# 1_-_Power.net
KiCad netlist of a schematic drawn in Altium Designer
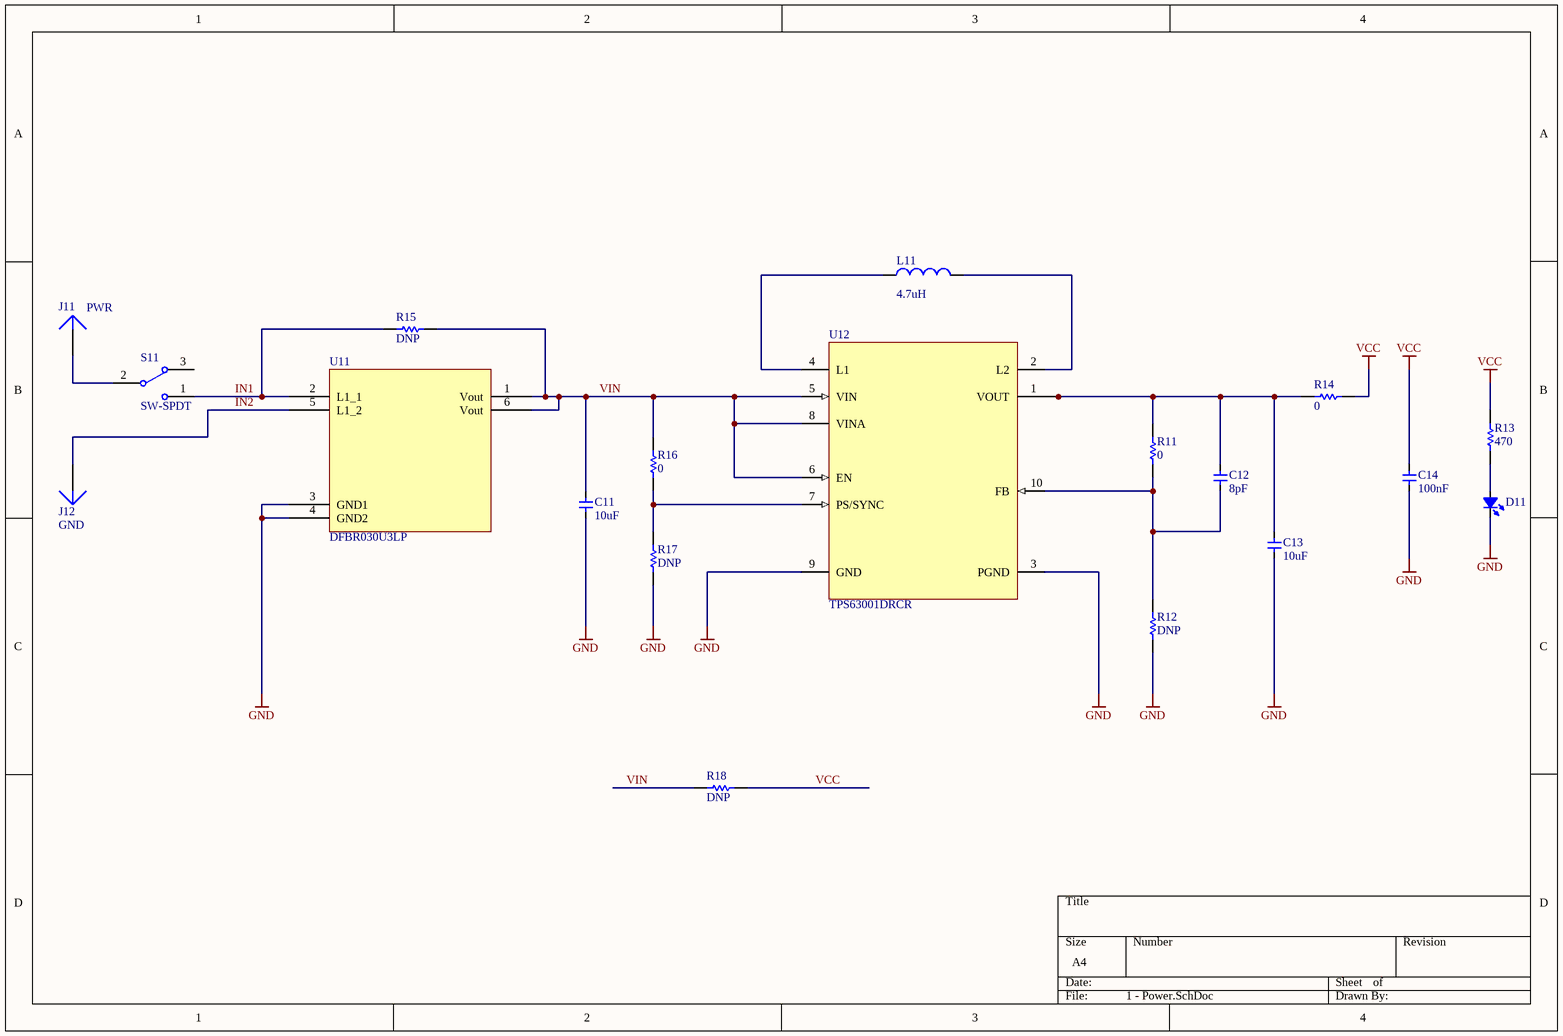
[diagram p0: 1 - Power.SchDoc]

(export (version "E")
  (design (tool "Eeschema 10.0.6"))
  (components
    (comp (ref "C11")
      (value "10uF")
      (footprint "CAPC2012X135N")
      (description "Capacitor")
      (fields (field (name "Comment") "Cap_0603"))
      (libsource (lib "SCH_Passive") (part "Cap_0603"))
    )
    (comp (ref "C12")
      (value "8pF")
      (footprint "PCB_PassiveCap:CAP_0603")
      (description "Capacitor")
      (fields (field (name "Comment") "Cap_0603"))
      (libsource (lib "SCH_Passive") (part "Cap_0603"))
    )
    (comp (ref "C13")
      (value "10uF")
      (footprint "CAPC2012X135N")
      (description "Capacitor")
      (fields (field (name "Comment") "Cap_0603"))
      (libsource (lib "SCH_Passive") (part "Cap_0603"))
    )
    (comp (ref "C14")
      (value "100nF")
      (footprint "PCB_PassiveCap:CAP_0603")
      (description "Capacitor")
      (fields (field (name "Comment") "Cap_0603"))
      (libsource (lib "SCH_Passive") (part "Cap_0603"))
    )
    (comp (ref "D11")
      (value "LED_0603")
      (footprint "PCB_ActiveLED:LED_0603_RED")
      (description "LED")
      (libsource (lib "SCH_Active") (part "LED_0603"))
    )
    (comp (ref "J11")
      (value "PWR")
      (footprint "PIN1")
      (description "Plug")
      (fields (field (name "PUBLISHER") "Altium Limited"))
      (libsource (lib "Miscellaneous Connectors") (part "Plug"))
    )
    (comp (ref "J12")
      (value "GND")
      (footprint "PIN1")
      (description "Plug")
      (fields (field (name "PUBLISHER") "Altium Limited"))
      (libsource (lib "Miscellaneous Connectors") (part "Plug"))
    )
    (comp (ref "L11")
      (value "4.7uH")
      (footprint "RES_0805")
      (description "Inductor")
      (fields (field (name "PUBLISHER") "Altium Limited"))
      (libsource (lib "Miscellaneous Devices") (part "Inductor"))
    )
    (comp (ref "R11")
      (value "0")
      (footprint "RES_0603")
      (description "Resistor")
      (fields (field (name "Comment") "Res1") (field (name "PUBLISHER") "Altium Limited"))
      (libsource (lib "Miscellaneous Devices") (part "Res1"))
    )
    (comp (ref "R12")
      (value "DNP")
      (footprint "RES_0603")
      (description "Resistor")
      (fields (field (name "Comment") "Res1") (field (name "PUBLISHER") "Altium Limited"))
      (libsource (lib "Miscellaneous Devices") (part "Res1"))
    )
    (comp (ref "R13")
      (value "470")
      (footprint "RES_0603")
      (description "Resistor")
      (fields (field (name "Comment") "Res1") (field (name "PUBLISHER") "Altium Limited"))
      (libsource (lib "Miscellaneous Devices") (part "Res1"))
    )
    (comp (ref "R14")
      (value "0")
      (footprint "RES_0603")
      (description "Resistor")
      (fields (field (name "Comment") "Res1") (field (name "PUBLISHER") "Altium Limited"))
      (libsource (lib "Miscellaneous Devices") (part "Res1"))
    )
    (comp (ref "R15")
      (value "DNP")
      (footprint "RES_0603")
      (description "Resistor")
      (fields (field (name "Comment") "Res1") (field (name "PUBLISHER") "Altium Limited"))
      (libsource (lib "Miscellaneous Devices") (part "Res1"))
    )
    (comp (ref "R16")
      (value "0")
      (footprint "RES_0603")
      (description "Resistor")
      (fields (field (name "Comment") "Res1") (field (name "PUBLISHER") "Altium Limited"))
      (libsource (lib "Miscellaneous Devices") (part "Res1"))
    )
    (comp (ref "R17")
      (value "DNP")
      (footprint "RES_0603")
      (description "Resistor")
      (fields (field (name "Comment") "Res1") (field (name "PUBLISHER") "Altium Limited"))
      (libsource (lib "Miscellaneous Devices") (part "Res1"))
    )
    (comp (ref "R18")
      (value "DNP")
      (footprint "RES_0603")
      (description "Resistor")
      (fields (field (name "Comment") "Res1") (field (name "PUBLISHER") "Altium Limited"))
      (libsource (lib "Miscellaneous Devices") (part "Res1"))
    )
    (comp (ref "S11")
      (value "SW-SPDT")
      (footprint "MSK-12C02")
      (description "SPDT Subminiature Toggle Switch, Right Angle Mounting, Vertical Actuation")
      (fields (field (name "PUBLISHER") "Altium Limited"))
      (libsource (lib "Jarrett") (part "SW-SPDT"))
    )
    (comp (ref "U11")
      (value "DFBR030U3LP")
      (footprint "Jarrett:U-DFN4040-8")
      (description "3A Full Bridge Rectifier")
      (libsource (lib "Jarrett") (part "DFBR030U3LP"))
    )
    (comp (ref "U12")
      (value "TPS63001DRCR")
      (footprint "10-VSON")
      (description "Buck-Boost Switching Regulator IC Positive Fixed 3.3V 1 Output 1.6A (Switch) 10-VFDFN Exposed Pad")
      (libsource (lib "Jarrett") (part "TPS63001DRCR"))
    )
  )
  (nets
    (net (code "1") (name "/IN1") (class "Default")
      (node (ref "R15") (pin "2") (pinfunction "2_2") (pintype "passive"))
      (node (ref "S11") (pin "1") (pinfunction "1_1") (pintype "passive"))
      (node (ref "U11") (pin "2") (pinfunction "L1_1_2") (pintype "passive"))
    )
    (net (code "2") (name "/IN2") (class "Default")
      (node (ref "J12") (pin "1") (pinfunction "1_1") (pintype "power_in"))
      (node (ref "U11") (pin "5") (pinfunction "L1_2_5") (pintype "passive"))
    )
    (net (code "3") (name "/VIN") (class "Default")
      (node (ref "C11") (pin "2") (pinfunction "2_2") (pintype "passive"))
      (node (ref "R15") (pin "1") (pinfunction "1_1") (pintype "passive"))
      (node (ref "R16") (pin "2") (pinfunction "2_2") (pintype "passive"))
      (node (ref "R18") (pin "2") (pinfunction "2_2") (pintype "passive"))
      (node (ref "U11") (pin "1") (pinfunction "Vout_1") (pintype "passive"))
      (node (ref "U11") (pin "6") (pinfunction "Vout_6") (pintype "passive"))
      (node (ref "U12") (pin "5") (pinfunction "VIN_5") (pintype "input"))
      (node (ref "U12") (pin "6") (pinfunction "EN_6") (pintype "input"))
      (node (ref "U12") (pin "8") (pinfunction "VINA_8") (pintype "power_in"))
    )
    (net (code "4") (name "GND") (class "Default")
      (node (ref "C11") (pin "1") (pinfunction "1_1") (pintype "passive"))
      (node (ref "C13") (pin "1") (pinfunction "1_1") (pintype "passive"))
      (node (ref "C14") (pin "1") (pinfunction "1_1") (pintype "passive"))
      (node (ref "D11") (pin "2") (pinfunction "K_2") (pintype "passive"))
      (node (ref "R12") (pin "1") (pinfunction "1_1") (pintype "passive"))
      (node (ref "R17") (pin "1") (pinfunction "1_1") (pintype "passive"))
      (node (ref "U11") (pin "3") (pinfunction "GND1_3") (pintype "passive"))
      (node (ref "U11") (pin "4") (pinfunction "GND2_4") (pintype "passive"))
      (node (ref "U12") (pin "3") (pinfunction "PGND_3") (pintype "power_in"))
      (node (ref "U12") (pin "9") (pinfunction "GND_9") (pintype "power_in"))
    )
    (net (code "5") (name "Net-(D11-A)") (class "Default")
      (node (ref "D11") (pin "1") (pinfunction "A_1") (pintype "passive"))
      (node (ref "R13") (pin "1") (pinfunction "1_1") (pintype "passive"))
    )
    (net (code "6") (name "Net-(J11-Pad1)") (class "Default")
      (node (ref "J11") (pin "1") (pinfunction "1_1") (pintype "power_in"))
      (node (ref "S11") (pin "2") (pinfunction "2_2") (pintype "passive"))
    )
    (net (code "7") (name "Net-(U12-FB)") (class "Default")
      (node (ref "C12") (pin "1") (pinfunction "1_1") (pintype "passive"))
      (node (ref "R11") (pin "1") (pinfunction "1_1") (pintype "passive"))
      (node (ref "R12") (pin "2") (pinfunction "2_2") (pintype "passive"))
      (node (ref "U12") (pin "10") (pinfunction "FB_10") (pintype "input"))
    )
    (net (code "8") (name "Net-(U12-L1)") (class "Default")
      (node (ref "L11") (pin "1") (pinfunction "1_1") (pintype "passive"))
      (node (ref "U12") (pin "4") (pinfunction "L1_4") (pintype "passive"))
    )
    (net (code "9") (name "Net-(U12-L2)") (class "Default")
      (node (ref "L11") (pin "2") (pinfunction "2_2") (pintype "passive"))
      (node (ref "U12") (pin "2") (pinfunction "L2_2") (pintype "passive"))
    )
    (net (code "10") (name "Net-(U12-PS{slash}SYNC)") (class "Default")
      (node (ref "R16") (pin "1") (pinfunction "1_1") (pintype "passive"))
      (node (ref "R17") (pin "2") (pinfunction "2_2") (pintype "passive"))
      (node (ref "U12") (pin "7") (pinfunction "PS/SYNC_7") (pintype "input"))
    )
    (net (code "11") (name "Net-(U12-VOUT)") (class "Default")
      (node (ref "C12") (pin "2") (pinfunction "2_2") (pintype "passive"))
      (node (ref "C13") (pin "2") (pinfunction "2_2") (pintype "passive"))
      (node (ref "R11") (pin "2") (pinfunction "2_2") (pintype "passive"))
      (node (ref "R14") (pin "2") (pinfunction "2_2") (pintype "passive"))
      (node (ref "U12") (pin "1") (pinfunction "VOUT_1") (pintype "power_in"))
    )
    (net (code "12") (name "VCC") (class "Default")
      (node (ref "C14") (pin "2") (pinfunction "2_2") (pintype "passive"))
      (node (ref "R13") (pin "2") (pinfunction "2_2") (pintype "passive"))
      (node (ref "R14") (pin "1") (pinfunction "1_1") (pintype "passive"))
      (node (ref "R18") (pin "1") (pinfunction "1_1") (pintype "passive"))
    )
    (net (code "13") (name "unconnected-(S11-Pad3)") (class "Default")
      (node (ref "S11") (pin "3") (pinfunction "3_3") (pintype "passive"))
    )
  )
)
